# Connectors.net
KiCad netlist of a schematic drawn in Altium Designer
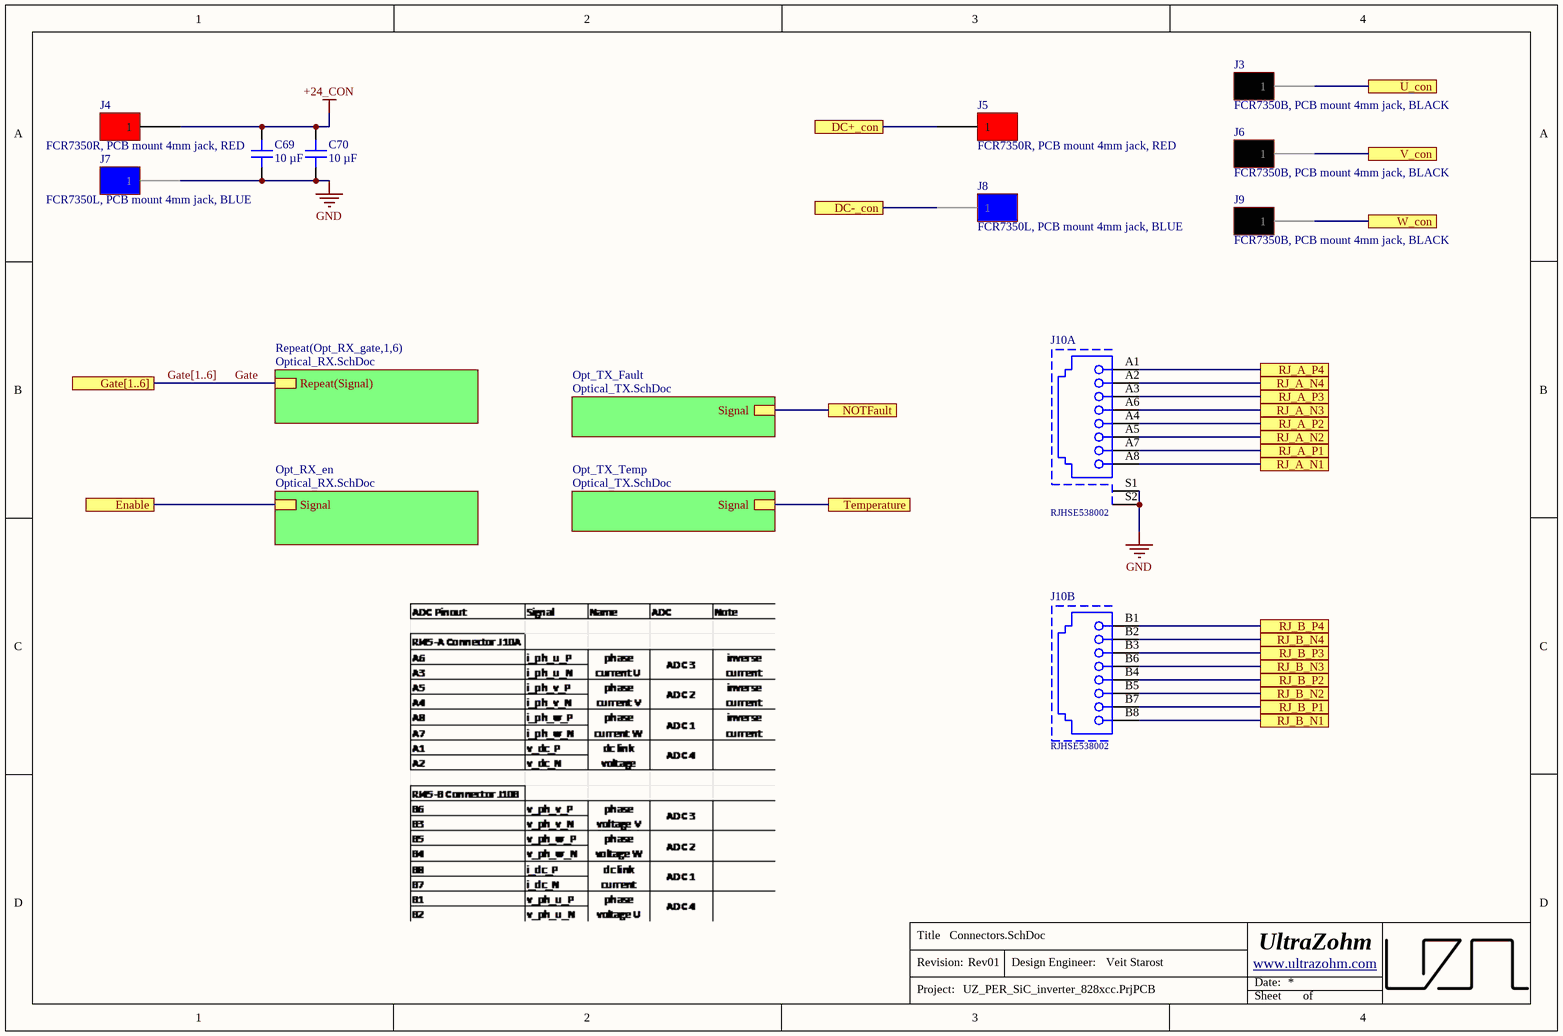
[diagram p0: Connectors.SchDoc]

(export (version "E")
  (design (tool "Eeschema 10.0.6"))
  (components
    (comp (ref "C69")
      (value "10 µF")
      (footprint "C_1206")
      (description "Capacitor 1206, 50 VDC, 10 µF, X7R")
      (fields
        (field (name "MANUFACTURER PART NUMBER") "CGA5L1X7R1H106K160AC")
        (field (name "MANUFACTURER") "TDK")
        (field (name "CREATED FROM") "MGremer")
      )
      (libsource (lib "user") (part "Capacitor"))
    )
    (comp (ref "C70")
      (value "10 µF")
      (footprint "C_1206")
      (description "Capacitor 1206, 50 VDC, 10 µF, X7R")
      (fields
        (field (name "MANUFACTURER PART NUMBER") "CGA5L1X7R1H106K160AC")
        (field (name "MANUFACTURER") "TDK")
        (field (name "CREATED FROM") "MGremer")
      )
      (libsource (lib "user") (part "Capacitor"))
    )
    (comp (ref "J3")
      (value "FCR7350B, PCB mount 4mm jack, BLACK")
      (footprint "FCR7350")
      (description "FCR7350B, 1000V, 24A, BLACK")
      (fields
        (field (name "MANUFACTURER PART NUMBER") "FCR7350B")
        (field (name "MANUFACTURER") "Cliff")
        (field (name "CREATED FROM") "DHufnagel")
      )
      (libsource (lib "user") (part "FCR7350B"))
    )
    (comp (ref "J4")
      (value "FCR7350R, PCB mount 4mm jack, RED")
      (footprint "FCR7350")
      (description "FCR7350B, 1000V, 24A, RED")
      (fields
        (field (name "MANUFACTURER PART NUMBER") "FCR7350R")
        (field (name "MANUFACTURER") "Cliff")
        (field (name "CREATED FROM") "DHufnagel")
      )
      (libsource (lib "user") (part "FCR7350R"))
    )
    (comp (ref "J5")
      (value "FCR7350R, PCB mount 4mm jack, RED")
      (footprint "FCR7350")
      (description "FCR7350B, 1000V, 24A, RED")
      (fields
        (field (name "MANUFACTURER PART NUMBER") "FCR7350R")
        (field (name "MANUFACTURER") "Cliff")
        (field (name "CREATED FROM") "DHufnagel")
      )
      (libsource (lib "") (part "FCR7350R_1"))
    )
    (comp (ref "J6")
      (value "FCR7350B, PCB mount 4mm jack, BLACK")
      (footprint "FCR7350")
      (description "FCR7350B, 1000V, 24A, BLACK")
      (fields
        (field (name "MANUFACTURER PART NUMBER") "FCR7350B")
        (field (name "MANUFACTURER") "Cliff")
        (field (name "CREATED FROM") "DHufnagel")
      )
      (libsource (lib "user") (part "FCR7350B"))
    )
    (comp (ref "J7")
      (value "FCR7350L, PCB mount 4mm jack, BLUE")
      (footprint "FCR7350")
      (description "FCR7350B, 1000V, 24A, BLUE")
      (fields
        (field (name "MANUFACTURER PART NUMBER") "FCR7350L")
        (field (name "MANUFACTURER") "Cliff")
        (field (name "CREATED FROM") "DHufnagel")
      )
      (libsource (lib "user") (part "FCR7350L"))
    )
    (comp (ref "J8")
      (value "FCR7350L, PCB mount 4mm jack, BLUE")
      (footprint "FCR7350")
      (description "FCR7350B, 1000V, 24A, BLUE")
      (fields
        (field (name "MANUFACTURER PART NUMBER") "FCR7350L")
        (field (name "MANUFACTURER") "Cliff")
        (field (name "CREATED FROM") "DHufnagel")
      )
      (libsource (lib "") (part "FCR7350L_1"))
    )
    (comp (ref "J9")
      (value "FCR7350B, PCB mount 4mm jack, BLACK")
      (footprint "FCR7350")
      (description "FCR7350B, 1000V, 24A, BLACK")
      (fields
        (field (name "MANUFACTURER PART NUMBER") "FCR7350B")
        (field (name "MANUFACTURER") "Cliff")
        (field (name "CREATED FROM") "DHufnagel")
      )
      (libsource (lib "user") (part "FCR7350B"))
    )
    (comp (ref "J10")
      (value "RJHSE538002")
      (footprint "RJHSE-5380-02")
      (description "CAT5, RJ45 Connector, 1x2")
      (fields (field (name "MANUFACTURER") "Amphenol") (field (name "CREATED FROM") "MGremer"))
      (libsource (lib "user") (part "RJHSE-5380-02"))
    )
  )
  (nets
    (net (code "7") (name "+24_CON") (class "Default")
      (node (ref "C69") (pin "2") (pinfunction "2_2") (pintype "passive"))
      (node (ref "C70") (pin "2") (pinfunction "2_2") (pintype "passive"))
      (node (ref "J4") (pin "1") (pinfunction "1_1") (pintype "passive"))
    )
    (net (code "8") (name "/DC+_con") (class "Default")
      (node (ref "J5") (pin "1") (pinfunction "1_1") (pintype "passive"))
    )
    (net (code "9") (name "/DC-_con") (class "Default")
      (node (ref "J8") (pin "1") (pinfunction "1_1") (pintype "passive"))
    )
    (net (code "14") (name "/RJ_A_N1") (class "Default")
      (node (ref "J10") (pin "A8") (pinfunction "A8_A8") (pintype "passive"))
    )
    (net (code "15") (name "/RJ_A_N2") (class "Default")
      (node (ref "J10") (pin "A5") (pinfunction "A5_A5") (pintype "passive"))
    )
    (net (code "16") (name "/RJ_A_N3") (class "Default")
      (node (ref "J10") (pin "A6") (pinfunction "A6_A6") (pintype "passive"))
    )
    (net (code "17") (name "/RJ_A_N4") (class "Default")
      (node (ref "J10") (pin "A2") (pinfunction "A2_A2") (pintype "passive"))
    )
    (net (code "18") (name "/RJ_A_P1") (class "Default")
      (node (ref "J10") (pin "A7") (pinfunction "A7_A7") (pintype "passive"))
    )
    (net (code "19") (name "/RJ_A_P2") (class "Default")
      (node (ref "J10") (pin "A4") (pinfunction "A4_A4") (pintype "passive"))
    )
    (net (code "20") (name "/RJ_A_P3") (class "Default")
      (node (ref "J10") (pin "A3") (pinfunction "A3_A3") (pintype "passive"))
    )
    (net (code "21") (name "/RJ_A_P4") (class "Default")
      (node (ref "J10") (pin "A1") (pinfunction "A1_A1") (pintype "passive"))
    )
    (net (code "22") (name "/RJ_B_N1") (class "Default")
      (node (ref "J10") (pin "B8") (pinfunction "B8_B8") (pintype "passive"))
    )
    (net (code "23") (name "/RJ_B_N2") (class "Default")
      (node (ref "J10") (pin "B5") (pinfunction "B5_B5") (pintype "passive"))
    )
    (net (code "24") (name "/RJ_B_N3") (class "Default")
      (node (ref "J10") (pin "B6") (pinfunction "B6_B6") (pintype "passive"))
    )
    (net (code "25") (name "/RJ_B_N4") (class "Default")
      (node (ref "J10") (pin "B2") (pinfunction "B2_B2") (pintype "passive"))
    )
    (net (code "26") (name "/RJ_B_P1") (class "Default")
      (node (ref "J10") (pin "B7") (pinfunction "B7_B7") (pintype "passive"))
    )
    (net (code "27") (name "/RJ_B_P2") (class "Default")
      (node (ref "J10") (pin "B4") (pinfunction "B4_B4") (pintype "passive"))
    )
    (net (code "28") (name "/RJ_B_P3") (class "Default")
      (node (ref "J10") (pin "B3") (pinfunction "B3_B3") (pintype "passive"))
    )
    (net (code "29") (name "/RJ_B_P4") (class "Default")
      (node (ref "J10") (pin "B1") (pinfunction "B1_B1") (pintype "passive"))
    )
    (net (code "31") (name "/U_con") (class "Default")
      (node (ref "J3") (pin "1") (pinfunction "1_1") (pintype "passive"))
    )
    (net (code "32") (name "/V_con") (class "Default")
      (node (ref "J6") (pin "1") (pinfunction "1_1") (pintype "passive"))
    )
    (net (code "33") (name "/W_con") (class "Default")
      (node (ref "J9") (pin "1") (pinfunction "1_1") (pintype "passive"))
    )
    (net (code "34") (name "GND") (class "Default")
      (node (ref "C69") (pin "1") (pinfunction "1_1") (pintype "passive"))
      (node (ref "C70") (pin "1") (pinfunction "1_1") (pintype "passive"))
      (node (ref "J10") (pin "S1") (pinfunction "S1_S1") (pintype "passive"))
      (node (ref "J10") (pin "S2") (pinfunction "S2_S2") (pintype "passive"))
      (node (ref "J7") (pin "1") (pinfunction "1_1") (pintype "passive"))
    )
  )
)
